# DDS_AD9854.net
KiCad netlist of a schematic drawn in Altium Designer
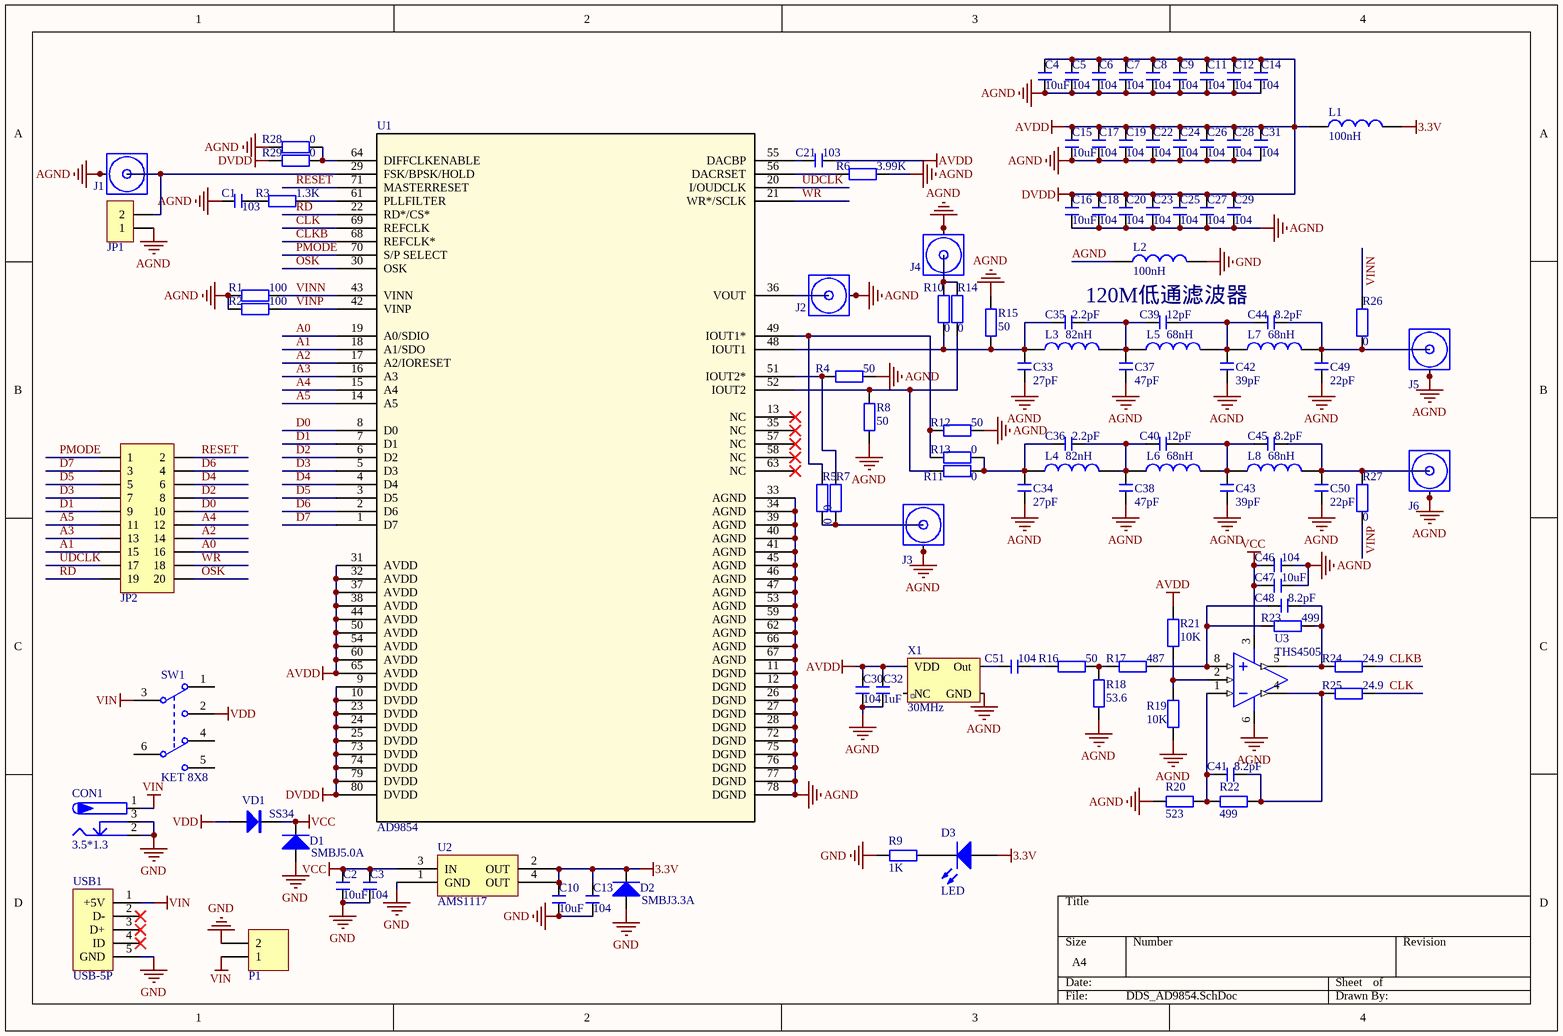
[diagram p0: DDS_AD9854.SchDoc]

(export (version "E")
  (design (tool "Eeschema 10.0.6"))
  (components
    (comp (ref "C1")
      (value "103")
      (footprint "C 0603")
      (description "无极性贴片电容")
      (fields (field (name "版权归属") "源创客"))
      (libsource (lib "电阻-电容-电感") (part "C"))
    )
    (comp (ref "C2")
      (value "10uF")
      (footprint "C 0805")
      (description "无极性贴片电容")
      (fields (field (name "版权归属") "源创客"))
      (libsource (lib "电阻-电容-电感") (part "C"))
    )
    (comp (ref "C3")
      (value "104")
      (footprint "C 0603")
      (description "无极性贴片电容")
      (fields (field (name "版权归属") "源创客"))
      (libsource (lib "电阻-电容-电感") (part "C"))
    )
    (comp (ref "C4")
      (value "10uF")
      (footprint "C 0603")
      (description "无极性贴片电容")
      (fields (field (name "版权归属") "源创客"))
      (libsource (lib "电阻-电容-电感") (part "C"))
    )
    (comp (ref "C5")
      (value "104")
      (footprint "C 0603")
      (description "无极性贴片电容")
      (fields (field (name "版权归属") "源创客"))
      (libsource (lib "电阻-电容-电感") (part "C"))
    )
    (comp (ref "C6")
      (value "104")
      (footprint "C 0603")
      (description "无极性贴片电容")
      (fields (field (name "版权归属") "源创客"))
      (libsource (lib "电阻-电容-电感") (part "C"))
    )
    (comp (ref "C7")
      (value "104")
      (footprint "C 0603")
      (description "无极性贴片电容")
      (fields (field (name "版权归属") "源创客"))
      (libsource (lib "电阻-电容-电感") (part "C"))
    )
    (comp (ref "C8")
      (value "104")
      (footprint "C 0603")
      (description "无极性贴片电容")
      (fields (field (name "版权归属") "源创客"))
      (libsource (lib "电阻-电容-电感") (part "C"))
    )
    (comp (ref "C9")
      (value "104")
      (footprint "C 0603")
      (description "无极性贴片电容")
      (fields (field (name "版权归属") "源创客"))
      (libsource (lib "电阻-电容-电感") (part "C"))
    )
    (comp (ref "C10")
      (value "10uF")
      (footprint "C 0603")
      (description "无极性贴片电容")
      (fields (field (name "版权归属") "源创客"))
      (libsource (lib "电阻-电容-电感") (part "C"))
    )
    (comp (ref "C11")
      (value "104")
      (footprint "C 0603")
      (description "无极性贴片电容")
      (fields (field (name "版权归属") "源创客"))
      (libsource (lib "电阻-电容-电感") (part "C"))
    )
    (comp (ref "C12")
      (value "104")
      (footprint "C 0603")
      (description "无极性贴片电容")
      (fields (field (name "版权归属") "源创客"))
      (libsource (lib "电阻-电容-电感") (part "C"))
    )
    (comp (ref "C13")
      (value "104")
      (footprint "C 0603")
      (description "无极性贴片电容")
      (fields (field (name "版权归属") "源创客"))
      (libsource (lib "电阻-电容-电感") (part "C"))
    )
    (comp (ref "C14")
      (value "104")
      (footprint "C 0603")
      (description "无极性贴片电容")
      (fields (field (name "版权归属") "源创客"))
      (libsource (lib "电阻-电容-电感") (part "C"))
    )
    (comp (ref "C15")
      (value "10uF")
      (footprint "C 0603")
      (description "无极性贴片电容")
      (fields (field (name "版权归属") "源创客"))
      (libsource (lib "电阻-电容-电感") (part "C"))
    )
    (comp (ref "C16")
      (value "10uF")
      (footprint "C 0603")
      (description "无极性贴片电容")
      (fields (field (name "版权归属") "源创客"))
      (libsource (lib "电阻-电容-电感") (part "C"))
    )
    (comp (ref "C17")
      (value "104")
      (footprint "C 0603")
      (description "无极性贴片电容")
      (fields (field (name "版权归属") "源创客"))
      (libsource (lib "电阻-电容-电感") (part "C"))
    )
    (comp (ref "C18")
      (value "104")
      (footprint "C 0603")
      (description "无极性贴片电容")
      (fields (field (name "版权归属") "源创客"))
      (libsource (lib "电阻-电容-电感") (part "C"))
    )
    (comp (ref "C19")
      (value "104")
      (footprint "C 0603")
      (description "无极性贴片电容")
      (fields (field (name "版权归属") "源创客"))
      (libsource (lib "电阻-电容-电感") (part "C"))
    )
    (comp (ref "C20")
      (value "104")
      (footprint "C 0603")
      (description "无极性贴片电容")
      (fields (field (name "版权归属") "源创客"))
      (libsource (lib "电阻-电容-电感") (part "C"))
    )
    (comp (ref "C21")
      (value "103")
      (footprint "C 0603")
      (description "无极性贴片电容")
      (fields (field (name "版权归属") "源创客"))
      (libsource (lib "电阻-电容-电感") (part "C"))
    )
    (comp (ref "C22")
      (value "104")
      (footprint "C 0603")
      (description "无极性贴片电容")
      (fields (field (name "版权归属") "源创客"))
      (libsource (lib "电阻-电容-电感") (part "C"))
    )
    (comp (ref "C23")
      (value "104")
      (footprint "C 0603")
      (description "无极性贴片电容")
      (fields (field (name "版权归属") "源创客"))
      (libsource (lib "电阻-电容-电感") (part "C"))
    )
    (comp (ref "C24")
      (value "104")
      (footprint "C 0603")
      (description "无极性贴片电容")
      (fields (field (name "版权归属") "源创客"))
      (libsource (lib "电阻-电容-电感") (part "C"))
    )
    (comp (ref "C25")
      (value "104")
      (footprint "C 0603")
      (description "无极性贴片电容")
      (fields (field (name "版权归属") "源创客"))
      (libsource (lib "电阻-电容-电感") (part "C"))
    )
    (comp (ref "C26")
      (value "104")
      (footprint "C 0603")
      (description "无极性贴片电容")
      (fields (field (name "版权归属") "源创客"))
      (libsource (lib "电阻-电容-电感") (part "C"))
    )
    (comp (ref "C27")
      (value "104")
      (footprint "C 0603")
      (description "无极性贴片电容")
      (fields (field (name "版权归属") "源创客"))
      (libsource (lib "电阻-电容-电感") (part "C"))
    )
    (comp (ref "C28")
      (value "104")
      (footprint "C 0603")
      (description "无极性贴片电容")
      (fields (field (name "版权归属") "源创客"))
      (libsource (lib "电阻-电容-电感") (part "C"))
    )
    (comp (ref "C29")
      (value "104")
      (footprint "C 0603")
      (description "无极性贴片电容")
      (fields (field (name "版权归属") "源创客"))
      (libsource (lib "电阻-电容-电感") (part "C"))
    )
    (comp (ref "C30")
      (value "104")
      (footprint "C 0603")
      (description "无极性贴片电容")
      (fields (field (name "版权归属") "源创客"))
      (libsource (lib "电阻-电容-电感") (part "C"))
    )
    (comp (ref "C31")
      (value "104")
      (footprint "C 0603")
      (description "无极性贴片电容")
      (fields (field (name "版权归属") "源创客"))
      (libsource (lib "电阻-电容-电感") (part "C"))
    )
    (comp (ref "C32")
      (value "1uF")
      (footprint "C 0603")
      (description "无极性贴片电容")
      (fields (field (name "版权归属") "源创客"))
      (libsource (lib "电阻-电容-电感") (part "C"))
    )
    (comp (ref "C33")
      (value "27pF")
      (footprint "C 0603")
      (description "无极性贴片电容")
      (fields (field (name "版权归属") "源创客"))
      (libsource (lib "电阻-电容-电感") (part "C"))
    )
    (comp (ref "C34")
      (value "27pF")
      (footprint "C 0603")
      (description "无极性贴片电容")
      (fields (field (name "版权归属") "源创客"))
      (libsource (lib "电阻-电容-电感") (part "C"))
    )
    (comp (ref "C35")
      (value "2.2pF")
      (footprint "C 0603")
      (description "无极性贴片电容")
      (fields (field (name "版权归属") "源创客"))
      (libsource (lib "电阻-电容-电感") (part "C"))
    )
    (comp (ref "C36")
      (value "2.2pF")
      (footprint "C 0603")
      (description "无极性贴片电容")
      (fields (field (name "版权归属") "源创客"))
      (libsource (lib "电阻-电容-电感") (part "C"))
    )
    (comp (ref "C37")
      (value "47pF")
      (footprint "C 0603")
      (description "无极性贴片电容")
      (fields (field (name "版权归属") "源创客"))
      (libsource (lib "电阻-电容-电感") (part "C"))
    )
    (comp (ref "C38")
      (value "47pF")
      (footprint "C 0603")
      (description "无极性贴片电容")
      (fields (field (name "版权归属") "源创客"))
      (libsource (lib "电阻-电容-电感") (part "C"))
    )
    (comp (ref "C39")
      (value "12pF")
      (footprint "C 0603")
      (description "无极性贴片电容")
      (fields (field (name "版权归属") "源创客"))
      (libsource (lib "电阻-电容-电感") (part "C"))
    )
    (comp (ref "C40")
      (value "12pF")
      (footprint "C 0603")
      (description "无极性贴片电容")
      (fields (field (name "版权归属") "源创客"))
      (libsource (lib "电阻-电容-电感") (part "C"))
    )
    (comp (ref "C41")
      (value "8.2pF")
      (footprint "C 0603")
      (description "无极性贴片电容")
      (fields (field (name "版权归属") "源创客"))
      (libsource (lib "电阻-电容-电感") (part "C"))
    )
    (comp (ref "C42")
      (value "39pF")
      (footprint "C 0603")
      (description "无极性贴片电容")
      (fields (field (name "版权归属") "源创客"))
      (libsource (lib "电阻-电容-电感") (part "C"))
    )
    (comp (ref "C43")
      (value "39pF")
      (footprint "C 0603")
      (description "无极性贴片电容")
      (fields (field (name "版权归属") "源创客"))
      (libsource (lib "电阻-电容-电感") (part "C"))
    )
    (comp (ref "C44")
      (value "8.2pF")
      (footprint "C 0603")
      (description "无极性贴片电容")
      (fields (field (name "版权归属") "源创客"))
      (libsource (lib "电阻-电容-电感") (part "C"))
    )
    (comp (ref "C45")
      (value "8.2pF")
      (footprint "C 0603")
      (description "无极性贴片电容")
      (fields (field (name "版权归属") "源创客"))
      (libsource (lib "电阻-电容-电感") (part "C"))
    )
    (comp (ref "C46")
      (value "104")
      (footprint "C 0603")
      (description "无极性贴片电容")
      (fields (field (name "版权归属") "源创客"))
      (libsource (lib "电阻-电容-电感") (part "C"))
    )
    (comp (ref "C47")
      (value "10uF")
      (footprint "C 0603")
      (description "无极性贴片电容")
      (fields (field (name "版权归属") "源创客"))
      (libsource (lib "电阻-电容-电感") (part "C"))
    )
    (comp (ref "C48")
      (value "8.2pF")
      (footprint "C 0603")
      (description "无极性贴片电容")
      (fields (field (name "版权归属") "源创客"))
      (libsource (lib "电阻-电容-电感") (part "C"))
    )
    (comp (ref "C49")
      (value "22pF")
      (footprint "C 0603")
      (description "无极性贴片电容")
      (fields (field (name "版权归属") "源创客"))
      (libsource (lib "电阻-电容-电感") (part "C"))
    )
    (comp (ref "C50")
      (value "22pF")
      (footprint "C 0603")
      (description "无极性贴片电容")
      (fields (field (name "版权归属") "源创客"))
      (libsource (lib "电阻-电容-电感") (part "C"))
    )
    (comp (ref "C51")
      (value "104")
      (footprint "C 0603")
      (description "无极性贴片电容")
      (fields (field (name "版权归属") "源创客"))
      (libsource (lib "电阻-电容-电感") (part "C"))
    )
    (comp (ref "CON1")
      (value "3.5*1.3")
      (footprint "DC-005")
      (description "低压电源接口")
      (fields (field (name "版权归属") "源创客"))
      (libsource (lib "接口类") (part "P-DC"))
    )
    (comp (ref "D1")
      (value "TVS")
      (footprint "SMB")
      (description "TVS保护")
      (fields (field (name "TYPE") "SMBJ5.0A") (field (name "PUBLISHER") "Altium Limited"))
      (libsource (lib "LIB") (part "TVS"))
    )
    (comp (ref "D2")
      (value "TVS")
      (footprint "SMB")
      (description "TVS保护")
      (fields (field (name "TYPE") "SMBJ3.3A") (field (name "PUBLISHER") "Altium Limited"))
      (libsource (lib "LIB") (part "TVS"))
    )
    (comp (ref "D3")
      (value "LED")
      (footprint "LED_0805")
      (description "发光二极管")
      (fields (field (name "PUBLISHER") "Altium Limited"))
      (libsource (lib "LIB") (part "LED"))
    )
    (comp (ref "J1") (value "COAX") (footprint "MCX5.08-5-H") (libsource (lib "LIB") (part "COAX")))
    (comp (ref "J2") (value "COAX") (footprint "MCX5.08-5-H") (libsource (lib "LIB") (part "COAX")))
    (comp (ref "J3") (value "COAX") (footprint "MCX5.08-5-H") (libsource (lib "LIB") (part "COAX")))
    (comp (ref "J4") (value "COAX") (footprint "MCX5.08-5-H") (libsource (lib "LIB") (part "COAX")))
    (comp (ref "J5") (value "COAX") (footprint "MCX5.08-5-H") (libsource (lib "LIB") (part "COAX")))
    (comp (ref "J6") (value "COAX") (footprint "MCX5.08-5-H") (libsource (lib "LIB") (part "COAX")))
    (comp (ref "JP1")
      (value "HDR-1X2")
      (footprint "HDR-1X2")
      (description "2P接插件")
      (fields (field (name "版权归属") "源创客"))
      (libsource (lib "接插件") (part "Header 2"))
    )
    (comp (ref "JP2")
      (value "Header 2X10")
      (footprint "HDR-10X2")
      (description "10*2P接插件")
      (fields (field (name "版权归属") "源创客"))
      (libsource (lib "接插件") (part "Header 10X2"))
    )
    (comp (ref "L1")
      (value "100nH")
      (footprint "L 0805")
      (description "小功率贴片电感")
      (fields (field (name "版权归属") "源创客"))
      (libsource (lib "电阻-电容-电感") (part "L"))
    )
    (comp (ref "L2")
      (value "100nH")
      (footprint "L 0805")
      (description "小功率贴片电感")
      (fields (field (name "版权归属") "源创客"))
      (libsource (lib "电阻-电容-电感") (part "L"))
    )
    (comp (ref "L3")
      (value "82nH")
      (footprint "L 0603")
      (description "小功率贴片电感")
      (fields (field (name "版权归属") "源创客"))
      (libsource (lib "电阻-电容-电感") (part "L"))
    )
    (comp (ref "L4")
      (value "82nH")
      (footprint "L 0603")
      (description "小功率贴片电感")
      (fields (field (name "版权归属") "源创客"))
      (libsource (lib "电阻-电容-电感") (part "L"))
    )
    (comp (ref "L5")
      (value "68nH")
      (footprint "L 0603")
      (description "小功率贴片电感")
      (fields (field (name "版权归属") "源创客"))
      (libsource (lib "电阻-电容-电感") (part "L"))
    )
    (comp (ref "L6")
      (value "68nH")
      (footprint "L 0603")
      (description "小功率贴片电感")
      (fields (field (name "版权归属") "源创客"))
      (libsource (lib "电阻-电容-电感") (part "L"))
    )
    (comp (ref "L7")
      (value "68nH")
      (footprint "L 0603")
      (description "小功率贴片电感")
      (fields (field (name "版权归属") "源创客"))
      (libsource (lib "电阻-电容-电感") (part "L"))
    )
    (comp (ref "L8")
      (value "68nH")
      (footprint "L 0603")
      (description "小功率贴片电感")
      (fields (field (name "版权归属") "源创客"))
      (libsource (lib "电阻-电容-电感") (part "L"))
    )
    (comp (ref "P1")
      (value "Header 2")
      (footprint "HDR2X1_B2")
      (description "接插件")
      (fields (field (name "PUBLISHER") "Altium Limited"))
      (libsource (lib "LIB") (part "Header 2"))
    )
    (comp (ref "R1")
      (value "100")
      (footprint "R 0603")
      (description "贴片电阻")
      (fields (field (name "版权归属") "源创客"))
      (libsource (lib "电阻-电容-电感") (part "R"))
    )
    (comp (ref "R2")
      (value "100")
      (footprint "R 0603")
      (description "贴片电阻")
      (fields (field (name "版权归属") "源创客"))
      (libsource (lib "电阻-电容-电感") (part "R"))
    )
    (comp (ref "R3")
      (value "1.3K")
      (footprint "R 0603")
      (description "贴片电阻")
      (fields (field (name "版权归属") "源创客"))
      (libsource (lib "电阻-电容-电感") (part "R"))
    )
    (comp (ref "R4")
      (value "50")
      (footprint "R 0603")
      (description "贴片电阻")
      (fields (field (name "版权归属") "源创客"))
      (libsource (lib "电阻-电容-电感") (part "R"))
    )
    (comp (ref "R5")
      (value "0")
      (footprint "R 0402")
      (description "贴片电阻")
      (fields (field (name "版权归属") "源创客"))
      (libsource (lib "电阻-电容-电感") (part "R"))
    )
    (comp (ref "R6")
      (value "3.99K")
      (footprint "R 0603")
      (description "贴片电阻")
      (fields (field (name "版权归属") "源创客"))
      (libsource (lib "电阻-电容-电感") (part "R"))
    )
    (comp (ref "R7")
      (value "0")
      (footprint "R 0402")
      (description "贴片电阻")
      (fields (field (name "版权归属") "源创客"))
      (libsource (lib "电阻-电容-电感") (part "R"))
    )
    (comp (ref "R8")
      (value "50")
      (footprint "R 0603")
      (description "贴片电阻")
      (fields (field (name "版权归属") "源创客"))
      (libsource (lib "电阻-电容-电感") (part "R"))
    )
    (comp (ref "R9")
      (value "1K")
      (footprint "R 0603")
      (description "贴片电阻")
      (fields (field (name "版权归属") "源创客"))
      (libsource (lib "电阻-电容-电感") (part "R"))
    )
    (comp (ref "R10")
      (value "0")
      (footprint "R 0402")
      (description "贴片电阻")
      (fields (field (name "版权归属") "源创客"))
      (libsource (lib "电阻-电容-电感") (part "R"))
    )
    (comp (ref "R11")
      (value "0")
      (footprint "R 0402")
      (description "贴片电阻")
      (fields (field (name "版权归属") "源创客"))
      (libsource (lib "电阻-电容-电感") (part "R"))
    )
    (comp (ref "R12")
      (value "50")
      (footprint "R 0603")
      (description "贴片电阻")
      (fields (field (name "版权归属") "源创客"))
      (libsource (lib "电阻-电容-电感") (part "R"))
    )
    (comp (ref "R13")
      (value "0")
      (footprint "R 0402")
      (description "贴片电阻")
      (fields (field (name "版权归属") "源创客"))
      (libsource (lib "电阻-电容-电感") (part "R"))
    )
    (comp (ref "R14")
      (value "0")
      (footprint "R 0402")
      (description "贴片电阻")
      (fields (field (name "版权归属") "源创客"))
      (libsource (lib "电阻-电容-电感") (part "R"))
    )
    (comp (ref "R15")
      (value "50")
      (footprint "R 0603")
      (description "贴片电阻")
      (fields (field (name "版权归属") "源创客"))
      (libsource (lib "电阻-电容-电感") (part "R"))
    )
    (comp (ref "R16")
      (value "50")
      (footprint "R 0603")
      (description "贴片电阻")
      (fields (field (name "版权归属") "源创客"))
      (libsource (lib "电阻-电容-电感") (part "R"))
    )
    (comp (ref "R17")
      (value "487")
      (footprint "R 0603")
      (description "贴片电阻")
      (fields (field (name "版权归属") "源创客"))
      (libsource (lib "电阻-电容-电感") (part "R"))
    )
    (comp (ref "R18")
      (value "53.6")
      (footprint "R 0603")
      (description "贴片电阻")
      (fields (field (name "版权归属") "源创客"))
      (libsource (lib "电阻-电容-电感") (part "R"))
    )
    (comp (ref "R19")
      (value "10K")
      (footprint "R 0603")
      (description "贴片电阻")
      (fields (field (name "版权归属") "源创客"))
      (libsource (lib "电阻-电容-电感") (part "R"))
    )
    (comp (ref "R20")
      (value "523")
      (footprint "R 0603")
      (description "贴片电阻")
      (fields (field (name "版权归属") "源创客"))
      (libsource (lib "电阻-电容-电感") (part "R"))
    )
    (comp (ref "R21")
      (value "10K")
      (footprint "R 0603")
      (description "贴片电阻")
      (fields (field (name "版权归属") "源创客"))
      (libsource (lib "电阻-电容-电感") (part "R"))
    )
    (comp (ref "R22")
      (value "499")
      (footprint "R 0603")
      (description "贴片电阻")
      (fields (field (name "版权归属") "源创客"))
      (libsource (lib "电阻-电容-电感") (part "R"))
    )
    (comp (ref "R23")
      (value "499")
      (footprint "R 0603")
      (description "贴片电阻")
      (fields (field (name "版权归属") "源创客"))
      (libsource (lib "电阻-电容-电感") (part "R"))
    )
    (comp (ref "R24")
      (value "24.9")
      (footprint "R 0603")
      (description "贴片电阻")
      (fields (field (name "版权归属") "源创客"))
      (libsource (lib "电阻-电容-电感") (part "R"))
    )
    (comp (ref "R25")
      (value "24.9")
      (footprint "R 0603")
      (description "贴片电阻")
      (fields (field (name "版权归属") "源创客"))
      (libsource (lib "电阻-电容-电感") (part "R"))
    )
    (comp (ref "R26")
      (value "0")
      (footprint "R 0402")
      (description "贴片电阻")
      (fields (field (name "版权归属") "源创客"))
      (libsource (lib "电阻-电容-电感") (part "R"))
    )
    (comp (ref "R27")
      (value "0")
      (footprint "R 0402")
      (description "贴片电阻")
      (fields (field (name "版权归属") "源创客"))
      (libsource (lib "电阻-电容-电感") (part "R"))
    )
    (comp (ref "R28")
      (value "0")
      (footprint "R 0402")
      (description "贴片电阻")
      (fields (field (name "版权归属") "源创客"))
      (libsource (lib "电阻-电容-电感") (part "R"))
    )
    (comp (ref "R29")
      (value "0")
      (footprint "R 0402")
      (description "贴片电阻")
      (fields (field (name "版权归属") "源创客"))
      (libsource (lib "电阻-电容-电感") (part "R"))
    )
    (comp (ref "SW1")
      (value "KET 8X8")
      (footprint "KFT DIP-8X8")
      (description "8*8自锁开关")
      (fields (field (name "版权归属") "源创客"))
      (libsource (lib "按键-开关") (part "KET 8X8"))
    )
    (comp (ref "U1")
      (value "AD9854")
      (footprint "LQFP-80_N")
      (description "DDS")
      (fields (field (name "MANUFACTURER_PART_NUMBER") "AD9854ASTZ"))
      (libsource (lib "LIB") (part "AD9854"))
    )
    (comp (ref "U2")
      (value "AMS1117")
      (footprint "SOT223_N")
      (description "线性稳压芯片")
      (libsource (lib "LIB") (part "ASM1117"))
    )
    (comp (ref "U3")
      (value "THS4505")
      (footprint "MSOP-MS8_M")
      (description "WIDEBAND, LOW-DISTORTION,FULLY DIFFERENTIAL AMPLIFIERS")
      (libsource (lib "LIB") (part "THS4505"))
    )
    (comp (ref "USB1")
      (value "USB-5P")
      (footprint "USB-MICRO_B")
      (description "微型USB母座")
      (fields (field (name "版权归属") "源创客"))
      (libsource (lib "接口类") (part "USB-5P"))
    )
    (comp (ref "VD1")
      (value "SS34")
      (footprint "DIODE-SMA")
      (description "肖特基二极管")
      (fields (field (name "版权归属") "源创客"))
      (libsource (lib "二极管-整流桥") (part "SS34"))
    )
    (comp (ref "X1")
      (value "XTAL")
      (footprint "X-CPX75")
      (description "有源晶振")
      (fields (field (name "FREQUENCY") "30MHz"))
      (libsource (lib "LIB") (part "XTAL_Oscillator"))
    )
  )
  (nets
    (net (code "1") (name "/A0") (class "Default")
      (node (ref "JP2") (pin "16") (pinfunction "16_16") (pintype "passive"))
      (node (ref "U1") (pin "19") (pinfunction "A0/SDIO_19") (pintype "passive"))
    )
    (net (code "2") (name "/A1") (class "Default")
      (node (ref "JP2") (pin "15") (pinfunction "15_15") (pintype "passive"))
      (node (ref "U1") (pin "18") (pinfunction "A1/SDO_18") (pintype "passive"))
    )
    (net (code "3") (name "/A2") (class "Default")
      (node (ref "JP2") (pin "14") (pinfunction "14_14") (pintype "passive"))
      (node (ref "U1") (pin "17") (pinfunction "A2/IORESET_17") (pintype "passive"))
    )
    (net (code "4") (name "/A3") (class "Default")
      (node (ref "JP2") (pin "13") (pinfunction "13_13") (pintype "passive"))
      (node (ref "U1") (pin "16") (pinfunction "A3_16") (pintype "passive"))
    )
    (net (code "5") (name "/A4") (class "Default")
      (node (ref "JP2") (pin "12") (pinfunction "12_12") (pintype "passive"))
      (node (ref "U1") (pin "15") (pinfunction "A4_15") (pintype "passive"))
    )
    (net (code "6") (name "/A5") (class "Default")
      (node (ref "JP2") (pin "11") (pinfunction "11_11") (pintype "passive"))
      (node (ref "U1") (pin "14") (pinfunction "A5_14") (pintype "passive"))
    )
    (net (code "7") (name "/CLK") (class "Default")
      (node (ref "R25") (pin "1") (pinfunction "1_1") (pintype "passive"))
      (node (ref "U1") (pin "69") (pinfunction "REFCLK_69") (pintype "passive"))
    )
    (net (code "8") (name "/CLKB") (class "Default")
      (node (ref "R24") (pin "1") (pinfunction "1_1") (pintype "passive"))
      (node (ref "U1") (pin "68") (pinfunction "REFCLK*_68") (pintype "passive"))
    )
    (net (code "9") (name "/D0") (class "Default")
      (node (ref "JP2") (pin "10") (pinfunction "10_10") (pintype "passive"))
      (node (ref "U1") (pin "8") (pinfunction "D0_8") (pintype "passive"))
    )
    (net (code "10") (name "/D1") (class "Default")
      (node (ref "JP2") (pin "9") (pinfunction "9_9") (pintype "passive"))
      (node (ref "U1") (pin "7") (pinfunction "D1_7") (pintype "passive"))
    )
    (net (code "11") (name "/D2") (class "Default")
      (node (ref "JP2") (pin "8") (pinfunction "8_8") (pintype "passive"))
      (node (ref "U1") (pin "6") (pinfunction "D2_6") (pintype "passive"))
    )
    (net (code "12") (name "/D3") (class "Default")
      (node (ref "JP2") (pin "7") (pinfunction "7_7") (pintype "passive"))
      (node (ref "U1") (pin "5") (pinfunction "D3_5") (pintype "passive"))
    )
    (net (code "13") (name "/D4") (class "Default")
      (node (ref "JP2") (pin "6") (pinfunction "6_6") (pintype "passive"))
      (node (ref "U1") (pin "4") (pinfunction "D4_4") (pintype "passive"))
    )
    (net (code "14") (name "/D5") (class "Default")
      (node (ref "JP2") (pin "5") (pinfunction "5_5") (pintype "passive"))
      (node (ref "U1") (pin "3") (pinfunction "D5_3") (pintype "passive"))
    )
    (net (code "15") (name "/D6") (class "Default")
      (node (ref "JP2") (pin "4") (pinfunction "4_4") (pintype "passive"))
      (node (ref "U1") (pin "2") (pinfunction "D6_2") (pintype "passive"))
    )
    (net (code "16") (name "/D7") (class "Default")
      (node (ref "JP2") (pin "3") (pinfunction "3_3") (pintype "passive"))
      (node (ref "U1") (pin "1") (pinfunction "D7_1") (pintype "passive"))
    )
    (net (code "17") (name "/OSK") (class "Default")
      (node (ref "JP2") (pin "20") (pinfunction "20_20") (pintype "passive"))
      (node (ref "U1") (pin "30") (pinfunction "OSK_30") (pintype "passive"))
    )
    (net (code "18") (name "/PMODE") (class "Default")
      (node (ref "JP2") (pin "1") (pinfunction "1_1") (pintype "passive"))
      (node (ref "U1") (pin "70") (pinfunction "S/P_SELECT_70") (pintype "passive"))
    )
    (net (code "19") (name "/RD") (class "Default")
      (node (ref "JP2") (pin "19") (pinfunction "19_19") (pintype "passive"))
      (node (ref "U1") (pin "22") (pinfunction "RD*/CS*_22") (pintype "passive"))
    )
    (net (code "20") (name "/RESET") (class "Default")
      (node (ref "JP2") (pin "2") (pinfunction "2_2") (pintype "passive"))
      (node (ref "U1") (pin "71") (pinfunction "MASTERRESET_71") (pintype "passive"))
    )
    (net (code "21") (name "/UDCLK") (class "Default")
      (node (ref "JP2") (pin "17") (pinfunction "17_17") (pintype "passive"))
      (node (ref "U1") (pin "20") (pinfunction "I/OUDCLK_20") (pintype "passive"))
    )
    (net (code "22") (name "/VINN") (class "Default")
      (node (ref "R1") (pin "1") (pinfunction "1_1") (pintype "passive"))
      (node (ref "R26") (pin "2") (pinfunction "2_2") (pintype "passive"))
      (node (ref "U1") (pin "43") (pinfunction "VINN_43") (pintype "passive"))
    )
    (net (code "23") (name "/VINP") (class "Default")
      (node (ref "R2") (pin "1") (pinfunction "1_1") (pintype "passive"))
      (node (ref "R27") (pin "1") (pinfunction "1_1") (pintype "passive"))
      (node (ref "U1") (pin "42") (pinfunction "VINP_42") (pintype "passive"))
    )
    (net (code "24") (name "/WR") (class "Default")
      (node (ref "JP2") (pin "18") (pinfunction "18_18") (pintype "passive"))
      (node (ref "U1") (pin "21") (pinfunction "WR*/SCLK_21") (pintype "passive"))
    )
    (net (code "25") (name "3.3V") (class "Default")
      (node (ref "C10") (pin "2") (pinfunction "2_2") (pintype "passive"))
      (node (ref "C13") (pin "2") (pinfunction "2_2") (pintype "passive"))
      (node (ref "D2") (pin "2") (pinfunction "K_2") (pintype "passive"))
      (node (ref "D3") (pin "1") (pinfunction "A_1") (pintype "passive"))
      (node (ref "L1") (pin "2") (pinfunction "2_2") (pintype "passive"))
      (node (ref "U2") (pin "2") (pinfunction "OUT_2") (pintype "passive"))
      (node (ref "U2") (pin "4") (pinfunction "OUT_4") (pintype "passive"))
    )
    (net (code "26") (name "AGND") (class "Default")
      (node (ref "C1") (pin "1") (pinfunction "1_1") (pintype "passive"))
      (node (ref "C11") (pin "1") (pinfunction "1_1") (pintype "passive"))
      (node (ref "C12") (pin "1") (pinfunction "1_1") (pintype "passive"))
      (node (ref "C14") (pin "1") (pinfunction "1_1") (pintype "passive"))
      (node (ref "C15") (pin "1") (pinfunction "1_1") (pintype "passive"))
      (node (ref "C16") (pin "1") (pinfunction "1_1") (pintype "passive"))
      (node (ref "C17") (pin "1") (pinfunction "1_1") (pintype "passive"))
      (node (ref "C18") (pin "1") (pinfunction "1_1") (pintype "passive"))
      (node (ref "C19") (pin "1") (pinfunction "1_1") (pintype "passive"))
      (node (ref "C20") (pin "1") (pinfunction "1_1") (pintype "passive"))
      (node (ref "C22") (pin "1") (pinfunction "1_1") (pintype "passive"))
      (node (ref "C23") (pin "1") (pinfunction "1_1") (pintype "passive"))
      (node (ref "C24") (pin "1") (pinfunction "1_1") (pintype "passive"))
      (node (ref "C25") (pin "1") (pinfunction "1_1") (pintype "passive"))
      (node (ref "C26") (pin "1") (pinfunction "1_1") (pintype "passive"))
      (node (ref "C27") (pin "1") (pinfunction "1_1") (pintype "passive"))
      (node (ref "C28") (pin "1") (pinfunction "1_1") (pintype "passive"))
      (node (ref "C29") (pin "1") (pinfunction "1_1") (pintype "passive"))
      (node (ref "C30") (pin "1") (pinfunction "1_1") (pintype "passive"))
      (node (ref "C31") (pin "1") (pinfunction "1_1") (pintype "passive"))
      (node (ref "C32") (pin "1") (pinfunction "1_1") (pintype "passive"))
      (node (ref "C33") (pin "1") (pinfunction "1_1") (pintype "passive"))
      (node (ref "C34") (pin "1") (pinfunction "1_1") (pintype "passive"))
      (node (ref "C37") (pin "2") (pinfunction "2_2") (pintype "passive"))
      (node (ref "C38") (pin "2") (pinfunction "2_2") (pintype "passive"))
      (node (ref "C4") (pin "1") (pinfunction "1_1") (pintype "passive"))
      (node (ref "C42") (pin "1") (pinfunction "1_1") (pintype "passive"))
      (node (ref "C43") (pin "1") (pinfunction "1_1") (pintype "passive"))
      (node (ref "C46") (pin "1") (pinfunction "1_1") (pintype "passive"))
      (node (ref "C47") (pin "1") (pinfunction "1_1") (pintype "passive"))
      (node (ref "C49") (pin "2") (pinfunction "2_2") (pintype "passive"))
      (node (ref "C5") (pin "1") (pinfunction "1_1") (pintype "passive"))
      (node (ref "C50") (pin "2") (pinfunction "2_2") (pintype "passive"))
      (node (ref "C6") (pin "1") (pinfunction "1_1") (pintype "passive"))
      (node (ref "C7") (pin "1") (pinfunction "1_1") (pintype "passive"))
      (node (ref "C8") (pin "1") (pinfunction "1_1") (pintype "passive"))
      (node (ref "C9") (pin "1") (pinfunction "1_1") (pintype "passive"))
      (node (ref "J1") (pin "2") (pinfunction "GND_2") (pintype "passive"))
      (node (ref "J1") (pin "3") (pinfunction "GND_3") (pintype "passive"))
      (node (ref "J1") (pin "4") (pinfunction "GND_4") (pintype "passive"))
      (node (ref "J1") (pin "5") (pinfunction "GND_5") (pintype "passive"))
      (node (ref "J2") (pin "2") (pinfunction "GND_2") (pintype "passive"))
      (node (ref "J2") (pin "3") (pinfunction "GND_3") (pintype "passive"))
      (node (ref "J2") (pin "4") (pinfunction "GND_4") (pintype "passive"))
      (node (ref "J2") (pin "5") (pinfunction "GND_5") (pintype "passive"))
      (node (ref "J3") (pin "2") (pinfunction "GND_2") (pintype "passive"))
      (node (ref "J3") (pin "3") (pinfunction "GND_3") (pintype "passive"))
      (node (ref "J3") (pin "4") (pinfunction "GND_4") (pintype "passive"))
      (node (ref "J3") (pin "5") (pinfunction "GND_5") (pintype "passive"))
      (node (ref "J4") (pin "2") (pinfunction "GND_2") (pintype "passive"))
      (node (ref "J4") (pin "3") (pinfunction "GND_3") (pintype "passive"))
      (node (ref "J4") (pin "4") (pinfunction "GND_4") (pintype "passive"))
      (node (ref "J4") (pin "5") (pinfunction "GND_5") (pintype "passive"))
      (node (ref "J5") (pin "2") (pinfunction "GND_2") (pintype "passive"))
      (node (ref "J5") (pin "3") (pinfunction "GND_3") (pintype "passive"))
      (node (ref "J5") (pin "4") (pinfunction "GND_4") (pintype "passive"))
      (node (ref "J5") (pin "5") (pinfunction "GND_5") (pintype "passive"))
      (node (ref "J6") (pin "2") (pinfunction "GND_2") (pintype "passive"))
      (node (ref "J6") (pin "3") (pinfunction "GND_3") (pintype "passive"))
      (node (ref "J6") (pin "4") (pinfunction "GND_4") (pintype "passive"))
      (node (ref "J6") (pin "5") (pinfunction "GND_5") (pintype "passive"))
      (node (ref "JP1") (pin "1") (pinfunction "1_1") (pintype "passive"))
      (node (ref "L2") (pin "1") (pinfunction "1_1") (pintype "passive"))
      (node (ref "R1") (pin "2") (pinfunction "2_2") (pintype "passive"))
      (node (ref "R12") (pin "1") (pinfunction "1_1") (pintype "passive"))
      (node (ref "R15") (pin "2") (pinfunction "2_2") (pintype "passive"))
      (node (ref "R18") (pin "2") (pinfunction "2_2") (pintype "passive"))
      (node (ref "R19") (pin "2") (pinfunction "2_2") (pintype "passive"))
      (node (ref "R2") (pin "2") (pinfunction "2_2") (pintype "passive"))
      (node (ref "R20") (pin "2") (pinfunction "2_2") (pintype "passive"))
      (node (ref "R28") (pin "1") (pinfunction "1_1") (pintype "passive"))
      (node (ref "R4") (pin "1") (pinfunction "1_1") (pintype "passive"))
      (node (ref "R6") (pin "2") (pinfunction "2_2") (pintype "passive"))
      (node (ref "R8") (pin "2") (pinfunction "2_2") (pintype "passive"))
      (node (ref "U1") (pin "11") (pinfunction "DGND_11") (pintype "passive"))
      (node (ref "U1") (pin "12") (pinfunction "DGND_12") (pintype "passive"))
      (node (ref "U1") (pin "26") (pinfunction "DGND_26") (pintype "passive"))
      (node (ref "U1") (pin "27") (pinfunction "DGND_27") (pintype "passive"))
      (node (ref "U1") (pin "28") (pinfunction "DGND_28") (pintype "passive"))
      (node (ref "U1") (pin "33") (pinfunction "AGND_33") (pintype "passive"))
      (node (ref "U1") (pin "34") (pinfunction "AGND_34") (pintype "passive"))
      (node (ref "U1") (pin "39") (pinfunction "AGND_39") (pintype "passive"))
      (node (ref "U1") (pin "40") (pinfunction "AGND_40") (pintype "passive"))
      (node (ref "U1") (pin "41") (pinfunction "AGND_41") (pintype "passive"))
      (node (ref "U1") (pin "45") (pinfunction "AGND_45") (pintype "passive"))
      (node (ref "U1") (pin "46") (pinfunction "AGND_46") (pintype "passive"))
      (node (ref "U1") (pin "47") (pinfunction "AGND_47") (pintype "passive"))
      (node (ref "U1") (pin "53") (pinfunction "AGND_53") (pintype "passive"))
      (node (ref "U1") (pin "59") (pinfunction "AGND_59") (pintype "passive"))
      (node (ref "U1") (pin "62") (pinfunction "AGND_62") (pintype "passive"))
      (node (ref "U1") (pin "66") (pinfunction "AGND_66") (pintype "passive"))
      (node (ref "U1") (pin "67") (pinfunction "AGND_67") (pintype "passive"))
      (node (ref "U1") (pin "72") (pinfunction "DGND_72") (pintype "passive"))
      (node (ref "U1") (pin "75") (pinfunction "DGND_75") (pintype "passive"))
      (node (ref "U1") (pin "76") (pinfunction "DGND_76") (pintype "passive"))
      (node (ref "U1") (pin "77") (pinfunction "DGND_77") (pintype "passive"))
      (node (ref "U1") (pin "78") (pinfunction "DGND_78") (pintype "passive"))
      (node (ref "U3") (pin "6") (pinfunction "VS-_6") (pintype "power_in"))
      (node (ref "X1") (pin "2") (pinfunction "GND_2") (pintype "passive"))
    )
    (net (code "27") (name "AVDD") (class "Default")
      (node (ref "C11") (pin "2") (pinfunction "2_2") (pintype "passive"))
      (node (ref "C12") (pin "2") (pinfunction "2_2") (pintype "passive"))
      (node (ref "C14") (pin "2") (pinfunction "2_2") (pintype "passive"))
      (node (ref "C15") (pin "2") (pinfunction "2_2") (pintype "passive"))
      (node (ref "C16") (pin "2") (pinfunction "2_2") (pintype "passive"))
      (node (ref "C17") (pin "2") (pinfunction "2_2") (pintype "passive"))
      (node (ref "C18") (pin "2") (pinfunction "2_2") (pintype "passive"))
      (node (ref "C19") (pin "2") (pinfunction "2_2") (pintype "passive"))
      (node (ref "C20") (pin "2") (pinfunction "2_2") (pintype "passive"))
      (node (ref "C21") (pin "2") (pinfunction "2_2") (pintype "passive"))
      (node (ref "C22") (pin "2") (pinfunction "2_2") (pintype "passive"))
      (node (ref "C23") (pin "2") (pinfunction "2_2") (pintype "passive"))
      (node (ref "C24") (pin "2") (pinfunction "2_2") (pintype "passive"))
      (node (ref "C25") (pin "2") (pinfunction "2_2") (pintype "passive"))
      (node (ref "C26") (pin "2") (pinfunction "2_2") (pintype "passive"))
      (node (ref "C27") (pin "2") (pinfunction "2_2") (pintype "passive"))
      (node (ref "C28") (pin "2") (pinfunction "2_2") (pintype "passive"))
      (node (ref "C29") (pin "2") (pinfunction "2_2") (pintype "passive"))
      (node (ref "C30") (pin "2") (pinfunction "2_2") (pintype "passive"))
      (node (ref "C31") (pin "2") (pinfunction "2_2") (pintype "passive"))
      (node (ref "C32") (pin "2") (pinfunction "2_2") (pintype "passive"))
      (node (ref "C4") (pin "2") (pinfunction "2_2") (pintype "passive"))
      (node (ref "C5") (pin "2") (pinfunction "2_2") (pintype "passive"))
      (node (ref "C6") (pin "2") (pinfunction "2_2") (pintype "passive"))
      (node (ref "C7") (pin "2") (pinfunction "2_2") (pintype "passive"))
      (node (ref "C8") (pin "2") (pinfunction "2_2") (pintype "passive"))
      (node (ref "C9") (pin "2") (pinfunction "2_2") (pintype "passive"))
      (node (ref "L1") (pin "1") (pinfunction "1_1") (pintype "passive"))
      (node (ref "R21") (pin "1") (pinfunction "1_1") (pintype "passive"))
      (node (ref "R29") (pin "1") (pinfunction "1_1") (pintype "passive"))
      (node (ref "U1") (pin "10") (pinfunction "DVDD_10") (pintype "power_in"))
      (node (ref "U1") (pin "23") (pinfunction "DVDD_23") (pintype "power_in"))
      (node (ref "U1") (pin "24") (pinfunction "DVDD_24") (pintype "power_in"))
      (node (ref "U1") (pin "25") (pinfunction "DVDD_25") (pintype "power_in"))
      (node (ref "U1") (pin "31") (pinfunction "AVDD_31") (pintype "power_in"))
      (node (ref "U1") (pin "32") (pinfunction "AVDD_32") (pintype "power_in"))
      (node (ref "U1") (pin "37") (pinfunction "AVDD_37") (pintype "power_in"))
      (node (ref "U1") (pin "38") (pinfunction "AVDD_38") (pintype "power_in"))
      (node (ref "U1") (pin "44") (pinfunction "AVDD_44") (pintype "power_in"))
      (node (ref "U1") (pin "50") (pinfunction "AVDD_50") (pintype "power_in"))
      (node (ref "U1") (pin "54") (pinfunction "AVDD_54") (pintype "power_in"))
      (node (ref "U1") (pin "60") (pinfunction "AVDD_60") (pintype "power_in"))
      (node (ref "U1") (pin "65") (pinfunction "AVDD_65") (pintype "power_in"))
      (node (ref "U1") (pin "73") (pinfunction "DVDD_73") (pintype "power_in"))
      (node (ref "U1") (pin "74") (pinfunction "DVDD_74") (pintype "power_in"))
      (node (ref "U1") (pin "79") (pinfunction "DVDD_79") (pintype "power_in"))
      (node (ref "U1") (pin "80") (pinfunction "DVDD_80") (pintype "power_in"))
      (node (ref "U1") (pin "9") (pinfunction "DVDD_9") (pintype "power_in"))
      (node (ref "X1") (pin "4") (pinfunction "VDD_4") (pintype "passive"))
    )
    (net (code "28") (name "GND") (class "Default")
      (node (ref "C10") (pin "1") (pinfunction "1_1") (pintype "passive"))
      (node (ref "C13") (pin "1") (pinfunction "1_1") (pintype "passive"))
      (node (ref "C2") (pin "1") (pinfunction "1_1") (pintype "passive"))
      (node (ref "C3") (pin "1") (pinfunction "1_1") (pintype "passive"))
      (node (ref "CON1") (pin "2") (pintype "power_in"))
      (node (ref "CON1") (pin "3") (pintype "power_in"))
      (node (ref "D1") (pin "1") (pinfunction "A_1") (pintype "passive"))
      (node (ref "D2") (pin "1") (pinfunction "A_1") (pintype "passive"))
      (node (ref "L2") (pin "2") (pinfunction "2_2") (pintype "passive"))
      (node (ref "P1") (pin "2") (pinfunction "2_2") (pintype "passive"))
      (node (ref "R9") (pin "2") (pinfunction "2_2") (pintype "passive"))
      (node (ref "U2") (pin "1") (pinfunction "GND_1") (pintype "passive"))
      (node (ref "USB1") (pin "5") (pinfunction "GND_5") (pintype "passive"))
    )
    (net (code "29") (name "Net-(C1-Pad2)") (class "Default")
      (node (ref "C1") (pin "2") (pinfunction "2_2") (pintype "passive"))
      (node (ref "R3") (pin "1") (pinfunction "1_1") (pintype "passive"))
    )
    (net (code "30") (name "Net-(C34-Pad2)") (class "Default")
      (node (ref "C34") (pin "2") (pinfunction "2_2") (pintype "passive"))
      (node (ref "C36") (pin "2") (pinfunction "2_2") (pintype "passive"))
      (node (ref "L4") (pin "1") (pinfunction "1_1") (pintype "passive"))
      (node (ref "R11") (pin "1") (pinfunction "1_1") (pintype "passive"))
      (node (ref "R13") (pin "1") (pinfunction "1_1") (pintype "passive"))
    )
    (net (code "31") (name "Net-(C35-Pad1)") (class "Default")
      (node (ref "C35") (pin "1") (pinfunction "1_1") (pintype "passive"))
      (node (ref "C37") (pin "1") (pinfunction "1_1") (pintype "passive"))
      (node (ref "C39") (pin "1") (pinfunction "1_1") (pintype "passive"))
      (node (ref "L3") (pin "2") (pinfunction "2_2") (pintype "passive"))
      (node (ref "L5") (pin "1") (pinfunction "1_1") (pintype "passive"))
    )
    (net (code "32") (name "Net-(C36-Pad1)") (class "Default")
      (node (ref "C36") (pin "1") (pinfunction "1_1") (pintype "passive"))
      (node (ref "C38") (pin "1") (pinfunction "1_1") (pintype "passive"))
      (node (ref "C40") (pin "1") (pinfunction "1_1") (pintype "passive"))
      (node (ref "L4") (pin "2") (pinfunction "2_2") (pintype "passive"))
      (node (ref "L6") (pin "1") (pinfunction "1_1") (pintype "passive"))
    )
    (net (code "33") (name "Net-(C39-Pad2)") (class "Default")
      (node (ref "C39") (pin "2") (pinfunction "2_2") (pintype "passive"))
      (node (ref "C42") (pin "2") (pinfunction "2_2") (pintype "passive"))
      (node (ref "C44") (pin "2") (pinfunction "2_2") (pintype "passive"))
      (node (ref "L5") (pin "2") (pinfunction "2_2") (pintype "passive"))
      (node (ref "L7") (pin "1") (pinfunction "1_1") (pintype "passive"))
    )
    (net (code "34") (name "Net-(C40-Pad2)") (class "Default")
      (node (ref "C40") (pin "2") (pinfunction "2_2") (pintype "passive"))
      (node (ref "C43") (pin "2") (pinfunction "2_2") (pintype "passive"))
      (node (ref "C45") (pin "2") (pinfunction "2_2") (pintype "passive"))
      (node (ref "L6") (pin "2") (pinfunction "2_2") (pintype "passive"))
      (node (ref "L8") (pin "1") (pinfunction "1_1") (pintype "passive"))
    )
    (net (code "35") (name "Net-(C48-Pad2)") (class "Default")
      (node (ref "C48") (pin "2") (pinfunction "2_2") (pintype "passive"))
      (node (ref "R17") (pin "1") (pinfunction "1_1") (pintype "passive"))
      (node (ref "R23") (pin "2") (pinfunction "2_2") (pintype "passive"))
      (node (ref "U3") (pin "8") (pinfunction "+IN_8") (pintype "input"))
    )
    (net (code "36") (name "Net-(C51-Pad1)") (class "Default")
      (node (ref "C51") (pin "1") (pinfunction "1_1") (pintype "passive"))
      (node (ref "R16") (pin "2") (pinfunction "2_2") (pintype "passive"))
    )
    (net (code "37") (name "Net-(D3-K)") (class "Default")
      (node (ref "D3") (pin "2") (pinfunction "K_2") (pintype "passive"))
      (node (ref "R9") (pin "1") (pinfunction "1_1") (pintype "passive"))
    )
    (net (code "38") (name "Net-(J1-Signal)") (class "Default")
      (node (ref "J1") (pin "1") (pinfunction "Signal_1") (pintype "passive"))
      (node (ref "JP1") (pin "2") (pinfunction "2_2") (pintype "passive"))
      (node (ref "U1") (pin "29") (pinfunction "FSK/BPSK/HOLD_29") (pintype "passive"))
    )
    (net (code "39") (name "Net-(J2-Signal)") (class "Default")
      (node (ref "J2") (pin "1") (pinfunction "Signal_1") (pintype "passive"))
      (node (ref "U1") (pin "36") (pinfunction "VOUT_36") (pintype "passive"))
    )
    (net (code "40") (name "Net-(J3-Signal)") (class "Default")
      (node (ref "J3") (pin "1") (pinfunction "Signal_1") (pintype "passive"))
      (node (ref "R5") (pin "1") (pinfunction "1_1") (pintype "passive"))
      (node (ref "R7") (pin "1") (pinfunction "1_1") (pintype "passive"))
    )
    (net (code "41") (name "Net-(J4-Signal)") (class "Default")
      (node (ref "J4") (pin "1") (pinfunction "Signal_1") (pintype "passive"))
      (node (ref "R10") (pin "2") (pinfunction "2_2") (pintype "passive"))
      (node (ref "R14") (pin "2") (pinfunction "2_2") (pintype "passive"))
    )
    (net (code "42") (name "Net-(J5-Signal)") (class "Default")
      (node (ref "C44") (pin "1") (pinfunction "1_1") (pintype "passive"))
      (node (ref "C49") (pin "1") (pinfunction "1_1") (pintype "passive"))
      (node (ref "J5") (pin "1") (pinfunction "Signal_1") (pintype "passive"))
      (node (ref "L7") (pin "2") (pinfunction "2_2") (pintype "passive"))
      (node (ref "R26") (pin "1") (pinfunction "1_1") (pintype "passive"))
    )
    (net (code "43") (name "Net-(J6-Signal)") (class "Default")
      (node (ref "C45") (pin "1") (pinfunction "1_1") (pintype "passive"))
      (node (ref "C50") (pin "1") (pinfunction "1_1") (pintype "passive"))
      (node (ref "J6") (pin "1") (pinfunction "Signal_1") (pintype "passive"))
      (node (ref "L8") (pin "2") (pinfunction "2_2") (pintype "passive"))
      (node (ref "R27") (pin "2") (pinfunction "2_2") (pintype "passive"))
    )
    (net (code "44") (name "Net-(R16-Pad1)") (class "Default")
      (node (ref "R16") (pin "1") (pinfunction "1_1") (pintype "passive"))
      (node (ref "R17") (pin "2") (pinfunction "2_2") (pintype "passive"))
      (node (ref "R18") (pin "1") (pinfunction "1_1") (pintype "passive"))
    )
    (net (code "45") (name "Net-(R19-Pad1)") (class "Default")
      (node (ref "R19") (pin "1") (pinfunction "1_1") (pintype "passive"))
      (node (ref "R21") (pin "2") (pinfunction "2_2") (pintype "passive"))
      (node (ref "U3") (pin "2") (pinfunction "+IN_2") (pintype "input"))
    )
    (net (code "46") (name "Net-(U1-DACBP)") (class "Default")
      (node (ref "C21") (pin "1") (pinfunction "1_1") (pintype "passive"))
      (node (ref "U1") (pin "55") (pinfunction "DACBP_55") (pintype "passive"))
    )
    (net (code "47") (name "Net-(U1-DACRSET)") (class "Default")
      (node (ref "R6") (pin "1") (pinfunction "1_1") (pintype "passive"))
      (node (ref "U1") (pin "56") (pinfunction "DACRSET_56") (pintype "passive"))
    )
    (net (code "48") (name "Net-(U1-DIFFCLKENABLE)") (class "Default")
      (node (ref "R28") (pin "2") (pinfunction "2_2") (pintype "passive"))
      (node (ref "R29") (pin "2") (pinfunction "2_2") (pintype "passive"))
      (node (ref "U1") (pin "64") (pinfunction "DIFFCLKENABLE_64") (pintype "passive"))
    )
    (net (code "49") (name "Net-(U1-IOUT1)") (class "Default")
      (node (ref "C33") (pin "2") (pinfunction "2_2") (pintype "passive"))
      (node (ref "C35") (pin "2") (pinfunction "2_2") (pintype "passive"))
      (node (ref "L3") (pin "1") (pinfunction "1_1") (pintype "passive"))
      (node (ref "R10") (pin "1") (pinfunction "1_1") (pintype "passive"))
      (node (ref "R15") (pin "1") (pinfunction "1_1") (pintype "passive"))
      (node (ref "U1") (pin "48") (pinfunction "IOUT1_48") (pintype "passive"))
    )
    (net (code "50") (name "Net-(U1-IOUT1*)") (class "Default")
      (node (ref "R12") (pin "2") (pinfunction "2_2") (pintype "passive"))
      (node (ref "R13") (pin "2") (pinfunction "2_2") (pintype "passive"))
      (node (ref "R5") (pin "2") (pinfunction "2_2") (pintype "passive"))
      (node (ref "U1") (pin "49") (pinfunction "IOUT1*_49") (pintype "passive"))
    )
    (net (code "51") (name "Net-(U1-IOUT2)") (class "Default")
      (node (ref "R11") (pin "2") (pinfunction "2_2") (pintype "passive"))
      (node (ref "R14") (pin "1") (pinfunction "1_1") (pintype "passive"))
      (node (ref "R8") (pin "1") (pinfunction "1_1") (pintype "passive"))
      (node (ref "U1") (pin "52") (pinfunction "IOUT2_52") (pintype "passive"))
    )
    (net (code "52") (name "Net-(U1-IOUT2*)") (class "Default")
      (node (ref "R4") (pin "2") (pinfunction "2_2") (pintype "passive"))
      (node (ref "R7") (pin "2") (pinfunction "2_2") (pintype "passive"))
      (node (ref "U1") (pin "51") (pinfunction "IOUT2*_51") (pintype "passive"))
    )
    (net (code "53") (name "Net-(U1-PLLFILTER)") (class "Default")
      (node (ref "R3") (pin "2") (pinfunction "2_2") (pintype "passive"))
      (node (ref "U1") (pin "61") (pinfunction "PLLFILTER_61") (pintype "passive"))
    )
    (net (code "54") (name "Net-(U3--IN)") (class "Default")
      (node (ref "C41") (pin "2") (pinfunction "2_2") (pintype "passive"))
      (node (ref "R20") (pin "1") (pinfunction "1_1") (pintype "passive"))
      (node (ref "R22") (pin "2") (pinfunction "2_2") (pintype "passive"))
      (node (ref "U3") (pin "1") (pinfunction "-IN_1") (pintype "input"))
    )
    (net (code "55") (name "Net-(U3-VOUT+)") (class "Default")
      (node (ref "C41") (pin "1") (pinfunction "1_1") (pintype "passive"))
      (node (ref "R22") (pin "1") (pinfunction "1_1") (pintype "passive"))
      (node (ref "R25") (pin "2") (pinfunction "2_2") (pintype "passive"))
      (node (ref "U3") (pin "4") (pinfunction "VOUT+_4") (pintype "output"))
    )
    (net (code "56") (name "Net-(U3-VOUT-)") (class "Default")
      (node (ref "C48") (pin "1") (pinfunction "1_1") (pintype "passive"))
      (node (ref "R23") (pin "1") (pinfunction "1_1") (pintype "passive"))
      (node (ref "R24") (pin "2") (pinfunction "2_2") (pintype "passive"))
      (node (ref "U3") (pin "5") (pinfunction "VOUT-_5") (pintype "output"))
    )
    (net (code "57") (name "Net-(X1-Out)") (class "Default")
      (node (ref "C51") (pin "2") (pinfunction "2_2") (pintype "passive"))
      (node (ref "X1") (pin "3") (pinfunction "Out_3") (pintype "passive"))
    )
    (net (code "58") (name "VCC") (class "Default")
      (node (ref "C2") (pin "2") (pinfunction "2_2") (pintype "passive"))
      (node (ref "C3") (pin "2") (pinfunction "2_2") (pintype "passive"))
      (node (ref "C46") (pin "2") (pinfunction "2_2") (pintype "passive"))
      (node (ref "C47") (pin "2") (pinfunction "2_2") (pintype "passive"))
      (node (ref "D1") (pin "2") (pinfunction "K_2") (pintype "passive"))
      (node (ref "U2") (pin "3") (pinfunction "IN_3") (pintype "passive"))
      (node (ref "U3") (pin "3") (pinfunction "VS+_3") (pintype "power_in"))
      (node (ref "VD1") (pin "2") (pinfunction "K_2") (pintype "passive"))
    )
    (net (code "59") (name "VDD") (class "Default")
      (node (ref "SW1") (pin "2") (pinfunction "COM2_2") (pintype "passive"))
      (node (ref "VD1") (pin "1") (pinfunction "A_1") (pintype "passive"))
    )
    (net (code "60") (name "VIN") (class "Default")
      (node (ref "CON1") (pin "1") (pintype "power_in"))
      (node (ref "P1") (pin "1") (pinfunction "1_1") (pintype "passive"))
      (node (ref "SW1") (pin "3") (pinfunction "NO1_3") (pintype "passive"))
      (node (ref "USB1") (pin "1") (pinfunction "+5V_1") (pintype "passive"))
    )
    (net (code "61") (name "unconnected-(SW1-COM2-Pad5)") (class "Default")
      (node (ref "SW1") (pin "5") (pinfunction "COM2_5") (pintype "passive"))
    )
    (net (code "62") (name "unconnected-(SW1-NC1-Pad1)") (class "Default")
      (node (ref "SW1") (pin "1") (pinfunction "NC1_1") (pintype "passive"))
    )
    (net (code "63") (name "unconnected-(SW1-NC2-Pad6)") (class "Default")
      (node (ref "SW1") (pin "6") (pinfunction "NC2_6") (pintype "passive"))
    )
    (net (code "64") (name "unconnected-(SW1-NO2-Pad4)") (class "Default")
      (node (ref "SW1") (pin "4") (pinfunction "NO2_4") (pintype "passive"))
    )
    (net (code "65") (name "unconnected-(U1-NC-Pad13)") (class "Default")
      (node (ref "U1") (pin "13") (pinfunction "NC_13") (pintype "passive+no_connect"))
    )
    (net (code "66") (name "unconnected-(U1-NC-Pad35)") (class "Default")
      (node (ref "U1") (pin "35") (pinfunction "NC_35") (pintype "passive+no_connect"))
    )
    (net (code "67") (name "unconnected-(U1-NC-Pad57)") (class "Default")
      (node (ref "U1") (pin "57") (pinfunction "NC_57") (pintype "passive+no_connect"))
    )
    (net (code "68") (name "unconnected-(U1-NC-Pad58)") (class "Default")
      (node (ref "U1") (pin "58") (pinfunction "NC_58") (pintype "passive+no_connect"))
    )
    (net (code "69") (name "unconnected-(U1-NC-Pad63)") (class "Default")
      (node (ref "U1") (pin "63") (pinfunction "NC_63") (pintype "passive+no_connect"))
    )
    (net (code "70") (name "unconnected-(USB1-D+-Pad3)") (class "Default")
      (node (ref "USB1") (pin "3") (pinfunction "D+_3") (pintype "passive+no_connect"))
    )
    (net (code "71") (name "unconnected-(USB1-D--Pad2)") (class "Default")
      (node (ref "USB1") (pin "2") (pinfunction "D-_2") (pintype "passive+no_connect"))
    )
    (net (code "72") (name "unconnected-(USB1-ID-Pad4)") (class "Default")
      (node (ref "USB1") (pin "4") (pinfunction "ID_4") (pintype "passive+no_connect"))
    )
    (net (code "73") (name "unconnected-(X1-NC-Pad1)") (class "Default")
      (node (ref "X1") (pin "1") (pinfunction "NC_1") (pintype "passive"))
    )
  )
)
